# Schematic.net
KiCad netlist of a schematic drawn in Altium Designer
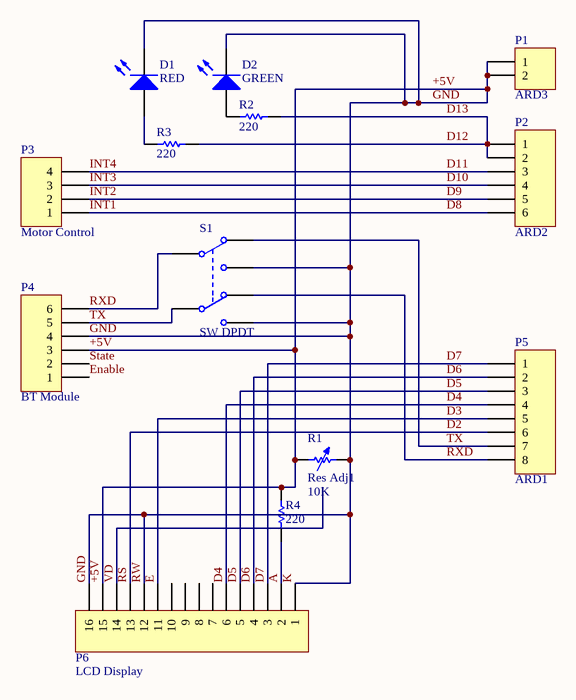
[diagram p0: Schematic.SchDoc]

(export (version "E")
  (design (tool "Eeschema 10.0.6"))
  (components
    (comp (ref "D1")
      (value "RED")
      (footprint "LED-0")
      (description "Typical INFRARED GaAs LED")
      (fields (field (name "PUBLISHER") "Altium Limited"))
      (libsource (lib "Miscellaneous Devices") (part "LED0"))
    )
    (comp (ref "D2")
      (value "GREEN")
      (footprint "LED-0")
      (description "Typical INFRARED GaAs LED")
      (fields (field (name "PUBLISHER") "Altium Limited"))
      (libsource (lib "Miscellaneous Devices") (part "LED0"))
    )
    (comp (ref "P1")
      (value "ARD3")
      (footprint "HDR1X2H")
      (description "Header, 2-Pin, Right Angle")
      (fields (field (name "PUBLISHER") "Altium Limited"))
      (libsource (lib "Miscellaneous Connectors") (part "Header 2H"))
    )
    (comp (ref "P2")
      (value "ARD2")
      (footprint "HDR1X6H")
      (description "Header, 6-Pin, Right Angle")
      (fields (field (name "PUBLISHER") "Altium Limited"))
      (libsource (lib "") (part "Header 6H_1"))
    )
    (comp (ref "P3")
      (value "Motor Control")
      (footprint "HDR1X4H")
      (description "Header, 4-Pin, Right Angle")
      (fields (field (name "PUBLISHER") "Altium Limited"))
      (libsource (lib "Miscellaneous Connectors") (part "Header 4H"))
    )
    (comp (ref "P4")
      (value "BT Module")
      (footprint "HDR1X6H")
      (description "Header, 6-Pin, Right Angle")
      (fields (field (name "PUBLISHER") "Altium Limited"))
      (libsource (lib "Miscellaneous Connectors") (part "Header 6H"))
    )
    (comp (ref "P5")
      (value "ARD1")
      (footprint "HDR1X8H")
      (description "Header, 8-Pin, Right Angle")
      (fields (field (name "PUBLISHER") "Altium Limited"))
      (libsource (lib "Miscellaneous Connectors") (part "Header 8H"))
    )
    (comp (ref "P6")
      (value "LCD Display")
      (footprint "HDR1X16")
      (description "Header, 16-Pin")
      (fields (field (name "PUBLISHER") "Altium Limited"))
      (libsource (lib "Miscellaneous Connectors") (part "Header 16"))
    )
    (comp (ref "R1")
      (value "Res Adj1")
      (footprint "AXIAL-0.7")
      (description "Variable Resistor")
      (fields (field (name "ALTIUM_VALUE") "10K") (field (name "PUBLISHER") "Altium Limited"))
      (libsource (lib "Miscellaneous Devices") (part "Res Adj1"))
    )
    (comp (ref "R2")
      (value "220")
      (footprint "AXIAL-0.3")
      (description "Resistor")
      (fields (field (name "PUBLISHER") "Altium Limited"))
      (libsource (lib "Miscellaneous Devices") (part "Res1"))
    )
    (comp (ref "R3")
      (value "220")
      (footprint "AXIAL-0.3")
      (description "Resistor")
      (fields (field (name "PUBLISHER") "Altium Limited"))
      (libsource (lib "Miscellaneous Devices") (part "Res1"))
    )
    (comp (ref "R4")
      (value "220")
      (footprint "AXIAL-0.3")
      (description "Resistor")
      (fields (field (name "PUBLISHER") "Altium Limited"))
      (libsource (lib "Miscellaneous Devices") (part "Res1"))
    )
    (comp (ref "S1")
      (value "SW DPDT")
      (footprint "SOT23-6_N")
      (description "Switch")
      (fields (field (name "PUBLISHER") "Altium Limited"))
      (libsource (lib "Miscellaneous Devices") (part "SW DPDT"))
    )
  )
  (nets
    (net (code "1") (name "/+5V") (class "Default")
      (node (ref "D1") (pin "2") (pinfunction "K_2") (pintype "passive"))
      (node (ref "D2") (pin "2") (pinfunction "K_2") (pintype "passive"))
      (node (ref "P1") (pin "1") (pinfunction "1_1") (pintype "passive"))
      (node (ref "P1") (pin "2") (pinfunction "2_2") (pintype "passive"))
      (node (ref "P4") (pin "3") (pinfunction "3_3") (pintype "passive"))
      (node (ref "P4") (pin "4") (pinfunction "4_4") (pintype "passive"))
      (node (ref "P6") (pin "1") (pinfunction "1_1") (pintype "passive"))
      (node (ref "P6") (pin "12") (pinfunction "12_12") (pintype "passive"))
      (node (ref "P6") (pin "15") (pinfunction "15_15") (pintype "passive"))
      (node (ref "P6") (pin "16") (pinfunction "16_16") (pintype "passive"))
      (node (ref "R1") (pin "1") (pinfunction "1_1") (pintype "passive"))
      (node (ref "R1") (pin "2") (pinfunction "2_2") (pintype "passive"))
      (node (ref "R4") (pin "1") (pinfunction "1_1") (pintype "passive"))
      (node (ref "S1") (pin "3") (pinfunction "NO1_3") (pintype "passive"))
      (node (ref "S1") (pin "6") (pinfunction "NO2_6") (pintype "passive"))
    )
    (net (code "2") (name "/A") (class "Default")
      (node (ref "P6") (pin "2") (pinfunction "2_2") (pintype "passive"))
      (node (ref "R4") (pin "2") (pinfunction "2_2") (pintype "passive"))
    )
    (net (code "3") (name "/D2") (class "Default")
      (node (ref "P5") (pin "6") (pinfunction "6_6") (pintype "passive"))
      (node (ref "P6") (pin "13") (pinfunction "13_13") (pintype "passive"))
    )
    (net (code "4") (name "/D3") (class "Default")
      (node (ref "P5") (pin "5") (pinfunction "5_5") (pintype "passive"))
      (node (ref "P6") (pin "11") (pinfunction "11_11") (pintype "passive"))
    )
    (net (code "5") (name "/D4") (class "Default")
      (node (ref "P5") (pin "4") (pinfunction "4_4") (pintype "passive"))
      (node (ref "P6") (pin "6") (pinfunction "6_6") (pintype "passive"))
    )
    (net (code "6") (name "/D5") (class "Default")
      (node (ref "P5") (pin "3") (pinfunction "3_3") (pintype "passive"))
      (node (ref "P6") (pin "5") (pinfunction "5_5") (pintype "passive"))
    )
    (net (code "7") (name "/D6") (class "Default")
      (node (ref "P5") (pin "2") (pinfunction "2_2") (pintype "passive"))
      (node (ref "P6") (pin "4") (pinfunction "4_4") (pintype "passive"))
    )
    (net (code "8") (name "/D7") (class "Default")
      (node (ref "P5") (pin "1") (pinfunction "1_1") (pintype "passive"))
      (node (ref "P6") (pin "3") (pinfunction "3_3") (pintype "passive"))
    )
    (net (code "9") (name "/D8") (class "Default")
      (node (ref "P2") (pin "6") (pinfunction "6_6") (pintype "passive"))
      (node (ref "P3") (pin "1") (pinfunction "1_1") (pintype "passive"))
    )
    (net (code "10") (name "/D9") (class "Default")
      (node (ref "P2") (pin "5") (pinfunction "5_5") (pintype "passive"))
      (node (ref "P3") (pin "2") (pinfunction "2_2") (pintype "passive"))
    )
    (net (code "11") (name "/D10") (class "Default")
      (node (ref "P2") (pin "4") (pinfunction "4_4") (pintype "passive"))
      (node (ref "P3") (pin "3") (pinfunction "3_3") (pintype "passive"))
    )
    (net (code "12") (name "/D11") (class "Default")
      (node (ref "P2") (pin "3") (pinfunction "3_3") (pintype "passive"))
      (node (ref "P3") (pin "4") (pinfunction "4_4") (pintype "passive"))
    )
    (net (code "13") (name "/D12") (class "Default")
      (node (ref "P2") (pin "1") (pinfunction "1_1") (pintype "passive"))
      (node (ref "P2") (pin "2") (pinfunction "2_2") (pintype "passive"))
      (node (ref "R2") (pin "1") (pinfunction "1_1") (pintype "passive"))
      (node (ref "R3") (pin "1") (pinfunction "1_1") (pintype "passive"))
    )
    (net (code "14") (name "/Enable") (class "Default")
      (node (ref "P4") (pin "1") (pinfunction "1_1") (pintype "passive"))
    )
    (net (code "15") (name "/RXD") (class "Default")
      (node (ref "P4") (pin "6") (pinfunction "6_6") (pintype "passive"))
      (node (ref "P5") (pin "8") (pinfunction "8_8") (pintype "passive"))
      (node (ref "S1") (pin "1") (pinfunction "COMMON1_1") (pintype "passive"))
      (node (ref "S1") (pin "4") (pinfunction "NC2_4") (pintype "passive"))
    )
    (net (code "16") (name "/State") (class "Default")
      (node (ref "P4") (pin "2") (pinfunction "2_2") (pintype "passive"))
    )
    (net (code "17") (name "/TX") (class "Default")
      (node (ref "P4") (pin "5") (pinfunction "5_5") (pintype "passive"))
      (node (ref "P5") (pin "7") (pinfunction "7_7") (pintype "passive"))
      (node (ref "S1") (pin "2") (pinfunction "NC1_2") (pintype "passive"))
      (node (ref "S1") (pin "5") (pinfunction "COMMON2_5") (pintype "passive"))
    )
    (net (code "18") (name "/VD") (class "Default")
      (node (ref "P6") (pin "14") (pinfunction "14_14") (pintype "passive"))
    )
    (net (code "19") (name "Net-(D1-A)") (class "Default")
      (node (ref "D1") (pin "1") (pinfunction "A_1") (pintype "passive"))
      (node (ref "R3") (pin "2") (pinfunction "2_2") (pintype "passive"))
    )
    (net (code "20") (name "Net-(D2-A)") (class "Default")
      (node (ref "D2") (pin "1") (pinfunction "A_1") (pintype "passive"))
      (node (ref "R2") (pin "2") (pinfunction "2_2") (pintype "passive"))
    )
    (net (code "21") (name "unconnected-(P6-Pad7)") (class "Default")
      (node (ref "P6") (pin "7") (pinfunction "7_7") (pintype "passive"))
    )
    (net (code "22") (name "unconnected-(P6-Pad8)") (class "Default")
      (node (ref "P6") (pin "8") (pinfunction "8_8") (pintype "passive"))
    )
    (net (code "23") (name "unconnected-(P6-Pad9)") (class "Default")
      (node (ref "P6") (pin "9") (pinfunction "9_9") (pintype "passive"))
    )
    (net (code "24") (name "unconnected-(P6-Pad10)") (class "Default")
      (node (ref "P6") (pin "10") (pinfunction "10_10") (pintype "passive"))
    )
  )
)
